# Sheet1.net
KiCad netlist of a schematic drawn in Altium Designer
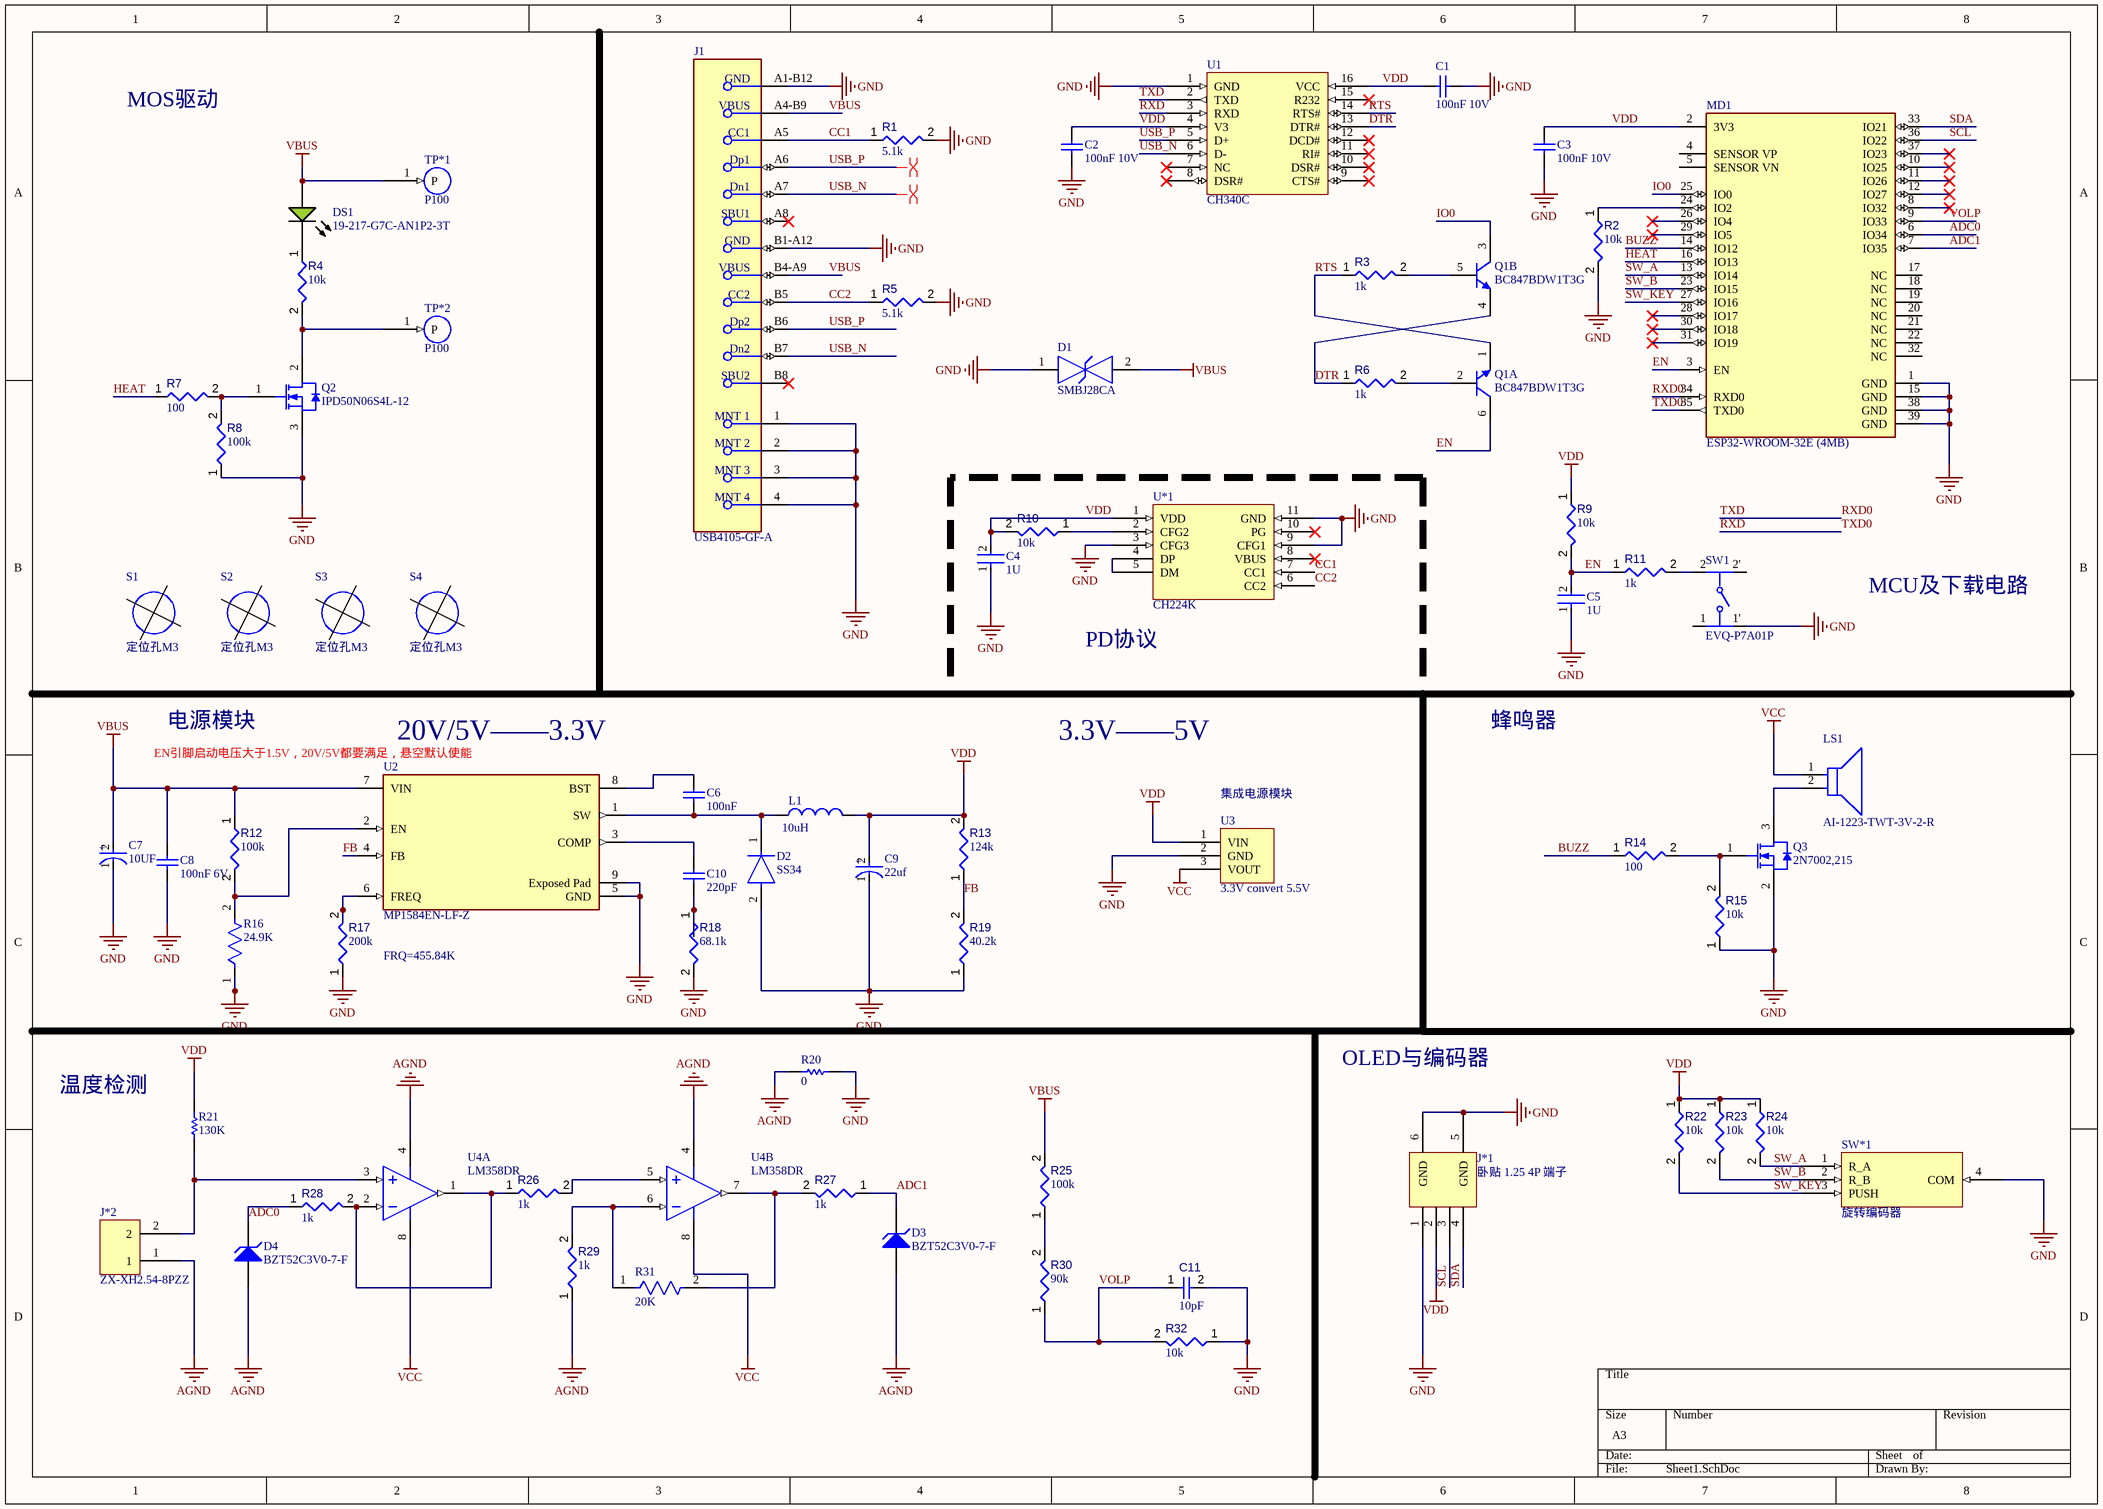
[diagram p0: Sheet1.SchDoc]

(export (version "E")
  (design (tool "Eeschema 10.0.6"))
  (components
    (comp (ref "C1")
      (value "100nF 10V")
      (footprint "CAPC0603(1608)100_M")
      (description "CAP 100nF 10V ±10% 0603 (1608 Metric) Thickness 1mm SMD")
      (fields (field (name "TOLERANCE") "Â±10%"))
      (libsource (lib "Altium Content Vault") (part "CAP"))
    )
    (comp (ref "C2")
      (value "100nF 10V")
      (footprint "CAPC0603(1608)100_M")
      (description "CAP 100nF 10V ±10% 0603 (1608 Metric) Thickness 1mm SMD")
      (fields (field (name "TOLERANCE") "Â±10%"))
      (libsource (lib "Altium Content Vault") (part "CAP"))
    )
    (comp (ref "C3")
      (value "100nF 10V")
      (footprint "CAPC0603(1608)100_M")
      (description "CAP 100nF 10V ±10% 0603 (1608 Metric) Thickness 1mm SMD")
      (fields (field (name "TOLERANCE") "Â±10%"))
      (libsource (lib "Altium Content Vault") (part "CAP"))
    )
    (comp (ref "C4")
      (value "1U")
      (footprint "FP-0603-L_1_6_0_15-W_0_81-IPC_A")
      (description "General Purpose Ceramic Capacitor, 0603, 1uF, 10%, X5R, 15%, 6.3V")
      (libsource (lib "Altium Content Vault") (part "02cd4be3c70576c341d710602a673aa"))
    )
    (comp (ref "C5")
      (value "1U")
      (footprint "FP-0603-L_1_6_0_15-W_0_81-IPC_A")
      (description "General Purpose Ceramic Capacitor, 0603, 1uF, 10%, X5R, 15%, 6.3V")
      (libsource (lib "Altium Content Vault") (part "02cd4be3c70576c341d710602a673aa"))
    )
    (comp (ref "C6")
      (value "100nF")
      (footprint "CAPC0603(1608)100_M")
      (description "CAP 100nF 10V ±10% 0603 (1608 Metric) Thickness 1mm SMD")
      (fields (field (name "TOLERANCE") "Â±10%"))
      (libsource (lib "Altium Content Vault") (part "CAP"))
    )
    (comp (ref "C7")
      (value "10UF")
      (footprint "FP-SC-MFG")
      (description "CAP ALUM 10UF 20% 35V SMD")
      (fields (field (name "TOLERANCE") "20%") (field (name "VOLTAGE") "35V"))
      (libsource (lib "Altium Content Vault") (part "203bc49f2ac43e59fd269a8c329ed05"))
    )
    (comp (ref "C8")
      (value "100nF 6V")
      (footprint "CAPC0603(1608)100_M")
      (description "CAP 100nF 10V ±10% 0603 (1608 Metric) Thickness 1mm SMD")
      (fields (field (name "TOLERANCE") "Â±10%"))
      (libsource (lib "Altium Content Vault") (part "CAP"))
    )
    (comp (ref "C9")
      (value "22uf")
      (footprint "FP-TAJC-MFG")
      (description "220uF 6.3V  ±10% 1.2Ω 2312  SMD Tantalum Capacitor")
      (fields (field (name "TOLERANCE") "10%") (field (name "VOLTAGE") "6.3V"))
      (libsource (lib "Altium Content Vault") (part "203bc49f2ac43e59fd269a8c329ed05"))
    )
    (comp (ref "C10")
      (value "220pF")
      (footprint "CAPC1608X90X35LL10T15")
      (fields (field (name "MANUFACTURER") "Murata") (field (name "PART NUMBER") "GRM1885C1H151JA01D"))
      (libsource (lib "Altium Content Vault") (part "CAP"))
    )
    (comp (ref "C11")
      (value "10pF")
      (footprint "CAPC1608X90X40ML10T20")
      (description "Chip Capacitor, 10 pF, +/- 5%, 50 V, 0603 (1608 Metric)")
      (fields (field (name "TOLERANCE") "5%") (field (name "Comment") "Capacitor 10 pF +/- 5% 50 V 0603"))
      (libsource (lib "DigiPCBA Workspace") (part "CAP-NP-2"))
    )
    (comp (ref "D1")
      (value "SMBJ28CA")
      (footprint "FP-SMBJ-CA-MFG")
      (description "TVS DIODE 28V 45.4V DO214AA")
      (fields
        (field (name "OCTOPART") "https://octopart.com/smbj28ca-littelfuse-350757")
        (field (name "MANUFACTURER") "Littelfuse Inc")
      )
      (libsource (lib "Altium Content Vault") (part "89c663e49c8877d2c9d183c2997548d"))
    )
    (comp (ref "D2")
      (value "SS34")
      (footprint "FP-95401-MFG")
      (description "DIODE GEN PURP 600V 2A DO214AA")
      (libsource (lib "Altium Content Vault") (part "d7152d700b627762746794eb795d46e"))
    )
    (comp (ref "D3")
      (value "BZT52C3V0-7-F")
      (footprint "DIOD-SOD123_V")
      (description "Surface Mount Zener Diode, 3 V, -65 to 150 degC, 2-Pin SOD123, RoHS, Tape and Reel")
      (fields (field (name "MANUFACTURER") "DiodesIncorporated"))
      (libsource (lib "Altium Content Vault") (part "DZEN-AK-2"))
    )
    (comp (ref "D4")
      (value "BZT52C3V0-7-F")
      (footprint "DIOD-SOD123_V")
      (description "Surface Mount Zener Diode, 3 V, -65 to 150 degC, 2-Pin SOD123, RoHS, Tape and Reel")
      (fields (field (name "MANUFACTURER") "DiodesIncorporated"))
      (libsource (lib "Altium Content Vault") (part "DZEN-AK-2"))
    )
    (comp (ref "DS1")
      (value "19-217-G7C-AN1P2-3T")
      (footprint "EVRL-0603-2_V")
      (description "Chip LED, Yellow-Green, 5 V, 25 mA, -40 to 85 degC, 2-Pin SMD (0603), RoHS, Tape and Reel")
      (fields (field (name "MANUFACTURER") "Everlight Electronics"))
      (libsource (lib "DigiPCBA Workspace") (part "LED-YELLOW-GREEN-AK-2"))
    )
    (comp (ref "J*1")
      (value "卧贴 1.25 4P 端子")
      (footprint "卧贴 1.25 4P 端子-Footprint-1")
      (description "ZX-MX1.25-4PJK")
      (libsource (lib "DigiPCBA Workspace") (part "卧贴 1.25 4P 端子-Symbol-1"))
    )
    (comp (ref "J*2")
      (value "ZX-XH2.54-8PZZ")
      (footprint "ZX-XH2.54-8PZZ-Footprint-1")
      (libsource (lib "DigiPCBA Workspace") (part "ZX-XH2.54-8PZZ-Symbol-1"))
    )
    (comp (ref "J1")
      (value "USB4105-GF-A")
      (footprint "FP-USB4105-GF-A-MFG")
      (description "CONN RCPT USB2.0 TYPEC 5A")
      (fields
        (field (name "MANUFACTURER") "GCT")
        (field (name "OCTOPART") "https://octopart.com/usb4105-gf-a-gct-106627878")
      )
      (libsource (lib "Altium Content Vault") (part "e7c17a616881a82b79941196b4bec10"))
    )
    (comp (ref "L1")
      (value "10uH")
      (footprint "INDM7266X28N")
      (description "SMD，7*6.6*2.8mm（0603） 合金电感，一体成型电感，大电流")
      (libsource (lib "DigiPCBA Workspace") (part "IND-2"))
    )
    (comp (ref "LS1")
      (value "AI-1223-TWT-3V-2-R")
      (footprint "FP-AI-1223-TWT-3V-2-R-MFG")
      (description "BUZZER MAGNETIC 3V 12MM TH")
      (libsource (lib "Altium Content Vault") (part "1973c4b650225fd2ddacaff6b763965"))
    )
    (comp (ref "MD1")
      (value "ESP32-WROOM-32E (4MB)")
      (footprint "FP-ESP32-WROOM-32E_4MB-MFG")
      (description "RX TXRX MOD WIFI TRACE ANT SMD")
      (libsource (lib "Altium Content Vault") (part "7f842c3463a9561e2f6f9fdcd687e0f"))
    )
    (comp (ref "Q1")
      (value "BC847BDW1T3G")
      (footprint "ONSC-SOT-363-6-419B-02_W_V")
      (description "Dual General Purpose Transistors, NPN, 6-Pin SOT-363, Pb-Free, Tape and Reel")
      (fields (field (name "MANUFACTURER") "On Semiconductor"))
      (libsource (lib "Altium Content Vault") (part "ONSC-NPN_NPN-6_F"))
    )
    (comp (ref "Q2")
      (value "IPD50N06S4L-12")
      (footprint "INF-PG-TO252-3-11_M")
      (description "OptiMOS-T2 Power-Transistor, 60 V VDS, 50 A ID, PG-TO252-3-11, Reel, Green")
      (fields (field (name "MANUFACTURER") "Infineon"))
      (libsource (lib "Altium Content Vault") (part "INF-MOSFET-N-3"))
    )
    (comp (ref "Q3")
      (value "2N7002,215")
      (footprint "NXP-SOT23-3_V")
      (fields (field (name "POWER") "830mW") (field (name "MANUFACTURER") "NXP Semiconductors"))
      (libsource (lib "DigiPCBA Workspace") (part "NEMOS-GSD-3"))
    )
    (comp (ref "R1")
      (value "5.1k")
      (footprint "RESC1608X55X25ML10T15")
      (description "Chip Resistor, 5.1 KOhm, +/- 1%, 0.1 W, -55 to 155 degC, 0603 (1608 Metric)")
      (fields (field (name "TOLERANCE") "1%") (field (name "POWER") "100mW"))
      (libsource (lib "DigiPCBA Workspace") (part "RES-2"))
    )
    (comp (ref "R2")
      (value "10k")
      (footprint "RESC1608X55X25ML10T15")
      (description "Chip Resistor, 4.7 KOhm, +/- 1%, 0.1 W, -55 to 155 degC, 0603 (1608 Metric)")
      (fields (field (name "TOLERANCE") "1%") (field (name "POWER") "100mW"))
      (libsource (lib "DigiPCBA Workspace") (part "RES-2"))
    )
    (comp (ref "R3")
      (value "1k")
      (footprint "RESC1608X55X25ML10T15")
      (description "Chip Resistor, 1 KOhm, +/-1%, 0.1 W, -55 to 155 degC, 0603 (1608 Metric)")
      (fields (field (name "POWER") "100mW") (field (name "TOLERANCE") "1%"))
      (libsource (lib "DigiPCBA Workspace") (part "RES-2"))
    )
    (comp (ref "R4")
      (value "10k")
      (footprint "RESC1608X55X25ML10T15")
      (description "Chip Resistor, 10 KOhm, +/- 1%, 01 W, -55 to 155 degC, 0603 (1608 Metric)")
      (fields (field (name "POWER") "100mW") (field (name "TOLERANCE") "1%"))
      (libsource (lib "DigiPCBA Workspace") (part "RES-2"))
    )
    (comp (ref "R5")
      (value "5.1k")
      (footprint "RESC1608X55X25ML10T15")
      (description "Chip Resistor, 4.7 KOhm, +/- 1%, 0.1 W, -55 to 155 degC, 0603 (1608 Metric)")
      (fields (field (name "TOLERANCE") "1%") (field (name "POWER") "100mW"))
      (libsource (lib "DigiPCBA Workspace") (part "RES-2"))
    )
    (comp (ref "R6")
      (value "1k")
      (footprint "RESC1608X55X25ML10T15")
      (description "Chip Resistor, 1 KOhm, +/-1%, 0.1 W, -55 to 155 degC, 0603 (1608 Metric)")
      (fields (field (name "POWER") "100mW") (field (name "TOLERANCE") "1%"))
      (libsource (lib "DigiPCBA Workspace") (part "RES-2"))
    )
    (comp (ref "R7")
      (value "100")
      (footprint "RESC0603(1608)_L")
      (description "120R 0.1W 5% 0603 (1608 Metric)  SMD")
      (fields (field (name "POWER") "100mW") (field (name "TOLERANCE") "5%"))
      (libsource (lib "DigiPCBA Workspace") (part "120R3J"))
    )
    (comp (ref "R8")
      (value "100k")
      (footprint "RESC1608X55X25ML10T15")
      (description "Chip Resistor, 100 KOhm, +/- 1%, 0.1 W, -55 to 155 degC, 0603 (1608 Metric)")
      (fields (field (name "TOLERANCE") "1%") (field (name "POWER") "100mW"))
      (libsource (lib "DigiPCBA Workspace") (part "RES-2"))
    )
    (comp (ref "R9")
      (value "10k")
      (footprint "RESC1608X55X25ML10T15")
      (description "Chip Resistor, 4.7 KOhm, +/- 1%, 0.1 W, -55 to 155 degC, 0603 (1608 Metric)")
      (fields (field (name "TOLERANCE") "1%") (field (name "POWER") "100mW"))
      (libsource (lib "DigiPCBA Workspace") (part "RES-2"))
    )
    (comp (ref "R10")
      (value "10k")
      (footprint "RESC1608X55X25ML10T15")
      (description "Chip Resistor, 4.7 KOhm, +/- 1%, 0.1 W, -55 to 155 degC, 0603 (1608 Metric)")
      (fields (field (name "TOLERANCE") "1%") (field (name "POWER") "100mW"))
      (libsource (lib "DigiPCBA Workspace") (part "RES-2"))
    )
    (comp (ref "R11")
      (value "1k")
      (footprint "RESC1608X55X25ML10T15")
      (description "Chip Resistor, 4.7 KOhm, +/- 1%, 0.1 W, -55 to 155 degC, 0603 (1608 Metric)")
      (fields (field (name "TOLERANCE") "1%") (field (name "POWER") "100mW"))
      (libsource (lib "DigiPCBA Workspace") (part "RES-2"))
    )
    (comp (ref "R12")
      (value "100k")
      (footprint "RESC1608X55X25ML10T15")
      (description "Chip Resistor, 100 KOhm, +/- 1%, 0.1 W, -55 to 155 degC, 0603 (1608 Metric)")
      (fields (field (name "TOLERANCE") "1%") (field (name "POWER") "100mW"))
      (libsource (lib "DigiPCBA Workspace") (part "RES-2"))
    )
    (comp (ref "R13")
      (value "124k")
      (footprint "RESC1608X55X25ML10T15")
      (description "Chip Resistor, 100 KOhm, +/- 1%, 0.1 W, -55 to 155 degC, 0603 (1608 Metric)")
      (fields (field (name "TOLERANCE") "1%") (field (name "POWER") "100mW"))
      (libsource (lib "DigiPCBA Workspace") (part "RES-2"))
    )
    (comp (ref "R14")
      (value "100")
      (footprint "RESC0603(1608)_L")
      (description "120R 0.1W 5% 0603 (1608 Metric)  SMD")
      (fields (field (name "POWER") "100mW") (field (name "TOLERANCE") "5%"))
      (libsource (lib "DigiPCBA Workspace") (part "120R3J"))
    )
    (comp (ref "R15")
      (value "10k")
      (footprint "RESC1608X55X25ML10T15")
      (description "Chip Resistor, 10 KOhm, +/- 1%, 01 W, -55 to 155 degC, 0603 (1608 Metric)")
      (fields (field (name "POWER") "100mW") (field (name "TOLERANCE") "1%"))
      (libsource (lib "DigiPCBA Workspace") (part "RES-2"))
    )
    (comp (ref "R16")
      (value "24.9K")
      (footprint "FP-RC_L0603-MFG")
      (description "RES SMD 24.9K OHM 1% 1/10W 0603")
      (fields (field (name "MANUFACTURER PART NUMBER") "RC0603FR-0724K9L") (field (name "VOLTAGE") "75V"))
      (libsource (lib "Altium Content Vault") (part "1029c3af85768c4190bb7ad29bc67b5"))
    )
    (comp (ref "R17")
      (value "200k")
      (footprint "RESC1608X55X25ML10T15")
      (description "Chip Resistor, 100 KOhm, +/- 1%, 0.1 W, -55 to 155 degC, 0603 (1608 Metric)")
      (fields (field (name "TOLERANCE") "1%") (field (name "POWER") "100mW"))
      (libsource (lib "DigiPCBA Workspace") (part "RES-2"))
    )
    (comp (ref "R18")
      (value "68.1k")
      (footprint "RESC1608X55X25ML10T15")
      (description "Chip Resistor, 100 KOhm, +/- 1%, 0.1 W, -55 to 155 degC, 0603 (1608 Metric)")
      (fields (field (name "TOLERANCE") "1%") (field (name "POWER") "100mW"))
      (libsource (lib "DigiPCBA Workspace") (part "RES-2"))
    )
    (comp (ref "R19")
      (value "40.2k")
      (footprint "RESC1608X55X25ML10T15")
      (description "Chip Resistor, 100 KOhm, +/- 1%, 0.1 W, -55 to 155 degC, 0603 (1608 Metric)")
      (fields (field (name "TOLERANCE") "1%") (field (name "POWER") "100mW"))
      (libsource (lib "DigiPCBA Workspace") (part "RES-2"))
    )
    (comp (ref "R20")
      (value "0")
      (footprint "RESC1608X55X25ML10T15")
      (description "Chip Resistor, 0 Ohm, 0.1 W, -55 to 155 degC, 0603 (1608 Metric)")
      (fields (field (name "POWER") "100mW") (field (name "TOLERANCE") "5%"))
      (libsource (lib "") (part "RES-2_1"))
    )
    (comp (ref "R21")
      (value "130K")
      (footprint "RESC1609X50X30NL10T20")
      (fields (field (name "MANUFACTURER") "Vishay Dale") (field (name "PART NUMBER") "CRCW0603130KFKEA"))
      (libsource (lib "Altium Content Vault") (part "RES"))
    )
    (comp (ref "R22")
      (value "10k")
      (footprint "RESC1608X55X25ML10T15")
      (description "Chip Resistor, 10 KOhm, +/- 1%, 01 W, -55 to 155 degC, 0603 (1608 Metric)")
      (fields (field (name "POWER") "100mW") (field (name "TOLERANCE") "1%"))
      (libsource (lib "DigiPCBA Workspace") (part "RES-2"))
    )
    (comp (ref "R23")
      (value "10k")
      (footprint "RESC1608X55X25ML10T15")
      (description "Chip Resistor, 10 KOhm, +/- 1%, 01 W, -55 to 155 degC, 0603 (1608 Metric)")
      (fields (field (name "POWER") "100mW") (field (name "TOLERANCE") "1%"))
      (libsource (lib "DigiPCBA Workspace") (part "RES-2"))
    )
    (comp (ref "R24")
      (value "10k")
      (footprint "RESC1608X55X25ML10T15")
      (description "Chip Resistor, 10 KOhm, +/- 1%, 01 W, -55 to 155 degC, 0603 (1608 Metric)")
      (fields (field (name "POWER") "100mW") (field (name "TOLERANCE") "1%"))
      (libsource (lib "DigiPCBA Workspace") (part "RES-2"))
    )
    (comp (ref "R25")
      (value "100k")
      (footprint "RESC1608X55X25ML10T15")
      (description "Chip Resistor, 100 KOhm, +/- 1%, 0.1 W, -55 to 155 degC, 0603 (1608 Metric)")
      (fields (field (name "TOLERANCE") "1%") (field (name "POWER") "100mW"))
      (libsource (lib "DigiPCBA Workspace") (part "RES-2"))
    )
    (comp (ref "R26")
      (value "1k")
      (footprint "RESC1608X55X25ML10T15")
      (description "Chip Resistor, 4.7 KOhm, +/- 1%, 0.1 W, -55 to 155 degC, 0603 (1608 Metric)")
      (fields (field (name "TOLERANCE") "1%") (field (name "POWER") "100mW"))
      (libsource (lib "DigiPCBA Workspace") (part "RES-2"))
    )
    (comp (ref "R27")
      (value "1k")
      (footprint "RESC1608X55X25ML10T15")
      (description "Chip Resistor, 4.7 KOhm, +/- 1%, 0.1 W, -55 to 155 degC, 0603 (1608 Metric)")
      (fields (field (name "TOLERANCE") "1%") (field (name "POWER") "100mW"))
      (libsource (lib "DigiPCBA Workspace") (part "RES-2"))
    )
    (comp (ref "R28")
      (value "1k")
      (footprint "RESC1608X55X25ML10T15")
      (description "Chip Resistor, 1 KOhm, +/-1%, 0.1 W, -55 to 155 degC, 0603 (1608 Metric)")
      (fields (field (name "POWER") "100mW") (field (name "TOLERANCE") "1%"))
      (libsource (lib "DigiPCBA Workspace") (part "RES-2"))
    )
    (comp (ref "R29")
      (value "1k")
      (footprint "RESC1608X55X25ML10T15")
      (description "Chip Resistor, 4.7 KOhm, +/- 1%, 0.1 W, -55 to 155 degC, 0603 (1608 Metric)")
      (fields (field (name "TOLERANCE") "1%") (field (name "POWER") "100mW"))
      (libsource (lib "DigiPCBA Workspace") (part "RES-2"))
    )
    (comp (ref "R30")
      (value "90k")
      (footprint "RESC1608X55X25ML10T15")
      (description "Chip Resistor, 100 KOhm, +/- 1%, 0.1 W, -55 to 155 degC, 0603 (1608 Metric)")
      (fields (field (name "TOLERANCE") "1%") (field (name "POWER") "100mW"))
      (libsource (lib "DigiPCBA Workspace") (part "RES-2"))
    )
    (comp (ref "R31")
      (value "20K")
      (footprint "FP-RC0603-0_55-IPC_C")
      (description "RES 20K OHM 1% 1/10W 0603")
      (libsource (lib "Altium Content Vault") (part "1029c3af85768c4190bb7ad29bc67b5"))
    )
    (comp (ref "R32")
      (value "10k")
      (footprint "RESC1608X55X25ML10T15")
      (description "Chip Resistor, 10 KOhm, +/- 1%, 01 W, -55 to 155 degC, 0603 (1608 Metric)")
      (fields (field (name "POWER") "100mW") (field (name "TOLERANCE") "1%"))
      (libsource (lib "DigiPCBA Workspace") (part "RES-2"))
    )
    (comp (ref "S1")
      (value "定位孔M3")
      (footprint "定位孔M3-Footprint-1")
      (description "M3定位孔")
      (libsource (lib "DigiPCBA Workspace") (part "定位孔M3-Symbol-1"))
    )
    (comp (ref "S2")
      (value "定位孔M3")
      (footprint "定位孔M3-Footprint-1")
      (description "M3定位孔")
      (libsource (lib "DigiPCBA Workspace") (part "定位孔M3-Symbol-1"))
    )
    (comp (ref "S3")
      (value "定位孔M3")
      (footprint "定位孔M3-Footprint-1")
      (description "M3定位孔")
      (libsource (lib "DigiPCBA Workspace") (part "定位孔M3-Symbol-1"))
    )
    (comp (ref "S4")
      (value "定位孔M3")
      (footprint "定位孔M3-Footprint-1")
      (description "M3定位孔")
      (libsource (lib "DigiPCBA Workspace") (part "定位孔M3-Symbol-1"))
    )
    (comp (ref "SW*1")
      (value "旋转编码器")
      (footprint "旋转编码器-Footprint-1")
      (description "MITSUMI  SIQ-02FVS3")
      (libsource (lib "DigiPCBA Workspace") (part "旋转编码器-Symbol-1"))
    )
    (comp (ref "SW1")
      (value "EVQ-P7A01P")
      (footprint "FP-EVQ-P7A01P-MFG")
      (description "Switch Tactile N.O. SPST Rectangular Button Gull Wing 0.05A 12VDC 2.2N SMD Embossed T/R")
      (libsource (lib "DigiPCBA Workspace") (part "c93661f14280f1e5a1fd29b4a471f7d"))
    )
    (comp (ref "TP*1")
      (value "P100")
      (footprint "P100-Footprint-1")
      (description "测试探针 3A")
      (libsource (lib "DigiPCBA Workspace") (part "P100-Symbol-1"))
    )
    (comp (ref "TP*2")
      (value "P100")
      (footprint "P100-Footprint-1")
      (description "测试探针 3A")
      (libsource (lib "DigiPCBA Workspace") (part "P100-Symbol-1"))
    )
    (comp (ref "U*1")
      (value "CH224K")
      (footprint "SOP100P610X180_HS-12N")
      (description "USB PD等多快充协议受电芯片CH224")
      (libsource (lib "DigiPCBA Workspace") (part "CH224K-Symbol-1"))
    )
    (comp (ref "U1")
      (value "CH340C")
      (footprint "SOP127P610X180-16N")
      (description "USB转串")
      (libsource (lib "DigiPCBA Workspace") (part "CH340C"))
    )
    (comp (ref "U2")
      (value "MP1584EN-LF-Z")
      (footprint "FP-MP1584EN-LF-Z-MFG")
      (description "IC REG BUCK ADJ 3A")
      (fields
        (field (name "OCTOPART") "https://octopart.com/mp1584en-lf-z-monolithic+power+systems-18629680")
        (field (name "MANUFACTURER") "Monolithic Power Systems")
      )
      (libsource (lib "Altium Content Vault") (part "4a11bbc70e04dd5d8e18f8ee926335f"))
    )
    (comp (ref "U3")
      (value "3.3V convert 5.5V")
      (footprint "3.3V convert 5.5V-Footprint-1")
      (description "迷你升压模块")
      (libsource (lib "DigiPCBA Workspace") (part "3.3V convert 5.5V-Symbol-1"))
    )
    (comp (ref "U4")
      (value "LM358DR")
      (footprint "D0008A_L")
      (fields (field (name "MANUFACTURER") "Texas Instruments (TI)"))
      (libsource (lib "DigiPCBA Workspace") (part "TI-LM358-8"))
    )
  )
  (nets
    (net (code "1") (name "/ADC0") (class "Default")
      (node (ref "D4") (pin "2") (pinfunction "K_2") (pintype "passive"))
      (node (ref "MD1") (pin "6") (pinfunction "IO34_6") (pintype "bidirectional"))
      (node (ref "R28") (pin "1") (pinfunction "1_1") (pintype "passive"))
    )
    (net (code "2") (name "/ADC1") (class "Default")
      (node (ref "D3") (pin "2") (pinfunction "K_2") (pintype "passive"))
      (node (ref "MD1") (pin "7") (pinfunction "IO35_7") (pintype "bidirectional"))
      (node (ref "R27") (pin "1") (pinfunction "1_1") (pintype "passive"))
    )
    (net (code "3") (name "/BUZZ") (class "Default")
      (node (ref "MD1") (pin "14") (pinfunction "IO12_14") (pintype "bidirectional"))
      (node (ref "R14") (pin "1") (pinfunction "1_1") (pintype "passive"))
    )
    (net (code "4") (name "/CC1") (class "Default")
      (node (ref "J1") (pin "A5") (pinfunction "CC1_A5") (pintype "power_in"))
      (node (ref "R1") (pin "1") (pinfunction "1_1") (pintype "passive"))
      (node (ref "U*1") (pin "7") (pinfunction "CC1_7") (pintype "input"))
    )
    (net (code "5") (name "/CC2") (class "Default")
      (node (ref "J1") (pin "B5") (pinfunction "CC2_B5") (pintype "bidirectional"))
      (node (ref "R5") (pin "1") (pinfunction "1_1") (pintype "passive"))
      (node (ref "U*1") (pin "6") (pinfunction "CC2_6") (pintype "input"))
    )
    (net (code "6") (name "/DTR") (class "Default")
      (node (ref "Q1") (pin "4") (pinfunction "E_4") (pintype "passive"))
      (node (ref "R6") (pin "1") (pinfunction "1_1") (pintype "passive"))
      (node (ref "U1") (pin "13") (pinfunction "DTR#_13") (pintype "bidirectional"))
    )
    (net (code "7") (name "/EN") (class "Default")
      (node (ref "C5") (pin "2") (pinfunction "2_2") (pintype "passive"))
      (node (ref "MD1") (pin "3") (pinfunction "EN_3") (pintype "input"))
      (node (ref "Q1") (pin "6") (pinfunction "C_6") (pintype "passive"))
      (node (ref "R11") (pin "1") (pinfunction "1_1") (pintype "passive"))
      (node (ref "R9") (pin "2") (pinfunction "2_2") (pintype "passive"))
    )
    (net (code "8") (name "/FB") (class "Default")
      (node (ref "R13") (pin "1") (pinfunction "1_1") (pintype "passive"))
      (node (ref "R19") (pin "2") (pinfunction "2_2") (pintype "passive"))
      (node (ref "U2") (pin "4") (pinfunction "FB_4") (pintype "input"))
    )
    (net (code "9") (name "/HEAT") (class "Default")
      (node (ref "MD1") (pin "16") (pinfunction "IO13_16") (pintype "bidirectional"))
      (node (ref "R7") (pin "1") (pinfunction "1_1") (pintype "passive"))
    )
    (net (code "10") (name "/IO0") (class "Default")
      (node (ref "MD1") (pin "25") (pinfunction "IO0_25") (pintype "bidirectional"))
      (node (ref "Q1") (pin "3") (pinfunction "C_3") (pintype "passive"))
    )
    (net (code "11") (name "/RTS") (class "Default")
      (node (ref "Q1") (pin "1") (pinfunction "E_1") (pintype "passive"))
      (node (ref "R3") (pin "1") (pinfunction "1_1") (pintype "passive"))
      (node (ref "U1") (pin "14") (pinfunction "RTS#_14") (pintype "bidirectional"))
    )
    (net (code "12") (name "/RXD") (class "Default")
      (node (ref "MD1") (pin "35") (pinfunction "TXD0_35") (pintype "output"))
      (node (ref "U1") (pin "3") (pinfunction "RXD_3") (pintype "input"))
    )
    (net (code "13") (name "/RXD0") (class "Default")
      (node (ref "MD1") (pin "34") (pinfunction "RXD0_34") (pintype "input"))
      (node (ref "U1") (pin "2") (pinfunction "TXD_2") (pintype "output"))
    )
    (net (code "14") (name "/SCL") (class "Default")
      (node (ref "J*1") (pin "3") (pinfunction "3_3") (pintype "passive"))
      (node (ref "MD1") (pin "36") (pinfunction "IO22_36") (pintype "bidirectional"))
    )
    (net (code "15") (name "/SDA") (class "Default")
      (node (ref "J*1") (pin "4") (pinfunction "4_4") (pintype "passive"))
      (node (ref "MD1") (pin "33") (pinfunction "IO21_33") (pintype "bidirectional"))
    )
    (net (code "16") (name "/SW_A") (class "Default")
      (node (ref "MD1") (pin "13") (pinfunction "IO14_13") (pintype "bidirectional"))
      (node (ref "R24") (pin "2") (pinfunction "2_2") (pintype "passive"))
      (node (ref "SW*1") (pin "1") (pinfunction "R_A_1") (pintype "input"))
    )
    (net (code "17") (name "/SW_B") (class "Default")
      (node (ref "MD1") (pin "23") (pinfunction "IO15_23") (pintype "bidirectional"))
      (node (ref "R23") (pin "2") (pinfunction "2_2") (pintype "passive"))
      (node (ref "SW*1") (pin "2") (pinfunction "R_B_2") (pintype "input"))
    )
    (net (code "18") (name "/SW_KEY") (class "Default")
      (node (ref "MD1") (pin "27") (pinfunction "IO16_27") (pintype "bidirectional"))
      (node (ref "R22") (pin "2") (pinfunction "2_2") (pintype "passive"))
      (node (ref "SW*1") (pin "3") (pinfunction "PUSH_3") (pintype "input"))
    )
    (net (code "19") (name "/USB_N") (class "Default")
      (node (ref "J1") (pin "A7") (pinfunction "Dn1_A7") (pintype "bidirectional"))
      (node (ref "J1") (pin "B7") (pinfunction "Dn2_B7") (pintype "bidirectional"))
      (node (ref "U1") (pin "6") (pinfunction "D-_6") (pintype "input"))
    )
    (net (code "20") (name "/USB_P") (class "Default")
      (node (ref "J1") (pin "A6") (pinfunction "Dp1_A6") (pintype "bidirectional"))
      (node (ref "J1") (pin "B6") (pinfunction "Dp2_B6") (pintype "bidirectional"))
      (node (ref "U1") (pin "5") (pinfunction "D+_5") (pintype "input"))
    )
    (net (code "21") (name "/VOLP") (class "Default")
      (node (ref "C11") (pin "1") (pinfunction "1_1") (pintype "passive"))
      (node (ref "MD1") (pin "9") (pinfunction "IO33_9") (pintype "bidirectional"))
      (node (ref "R30") (pin "1") (pinfunction "1_1") (pintype "passive"))
      (node (ref "R32") (pin "2") (pinfunction "2_2") (pintype "passive"))
    )
    (net (code "22") (name "AGND") (class "Default")
      (node (ref "D3") (pin "1") (pinfunction "A_1") (pintype "passive"))
      (node (ref "D4") (pin "1") (pinfunction "A_1") (pintype "passive"))
      (node (ref "J*2") (pin "1") (pinfunction "1_1") (pintype "passive"))
      (node (ref "R20") (pin "1") (pinfunction "1_1") (pintype "passive"))
      (node (ref "R29") (pin "1") (pinfunction "1_1") (pintype "passive"))
      (node (ref "U4") (pin "4") (pinfunction "GND_4") (pintype "power_in"))
    )
    (net (code "23") (name "GND") (class "Default")
      (node (ref "C1") (pin "2") (pinfunction "2_2") (pintype "passive"))
      (node (ref "C11") (pin "2") (pinfunction "2_2") (pintype "passive"))
      (node (ref "C2") (pin "1") (pinfunction "1_1") (pintype "passive"))
      (node (ref "C3") (pin "2") (pinfunction "2_2") (pintype "passive"))
      (node (ref "C4") (pin "1") (pinfunction "1_1") (pintype "passive"))
      (node (ref "C5") (pin "1") (pinfunction "1_1") (pintype "passive"))
      (node (ref "C7") (pin "1") (pinfunction "C_1") (pintype "passive"))
      (node (ref "C8") (pin "1") (pinfunction "1_1") (pintype "passive"))
      (node (ref "C9") (pin "1") (pinfunction "C_1") (pintype "passive"))
      (node (ref "D1") (pin "1") (pinfunction "1_1") (pintype "passive"))
      (node (ref "D2") (pin "2") (pinfunction "A_2") (pintype "passive"))
      (node (ref "J*1") (pin "1") (pinfunction "1_1") (pintype "passive"))
      (node (ref "J*1") (pin "5") (pinfunction "GND_5") (pintype "passive"))
      (node (ref "J*1") (pin "6") (pinfunction "GND_6") (pintype "passive"))
      (node (ref "J1") (pin "1") (pinfunction "MNT_1_1") (pintype "power_in"))
      (node (ref "J1") (pin "2") (pinfunction "MNT_2_2") (pintype "power_in"))
      (node (ref "J1") (pin "3") (pinfunction "MNT_3_3") (pintype "power_in"))
      (node (ref "J1") (pin "4") (pinfunction "MNT_4_4") (pintype "power_in"))
      (node (ref "J1") (pin "A1-B12") (pinfunction "GND_A1-B12") (pintype "power_in"))
      (node (ref "J1") (pin "B1-A12") (pinfunction "GND_B1-A12") (pintype "bidirectional"))
      (node (ref "MD1") (pin "1") (pinfunction "GND_1") (pintype "power_in"))
      (node (ref "MD1") (pin "15") (pinfunction "GND_15") (pintype "power_in"))
      (node (ref "MD1") (pin "38") (pinfunction "GND_38") (pintype "power_in"))
      (node (ref "MD1") (pin "39") (pinfunction "GND_39") (pintype "power_in"))
      (node (ref "Q2") (pin "3") (pinfunction "SOURCE_3") (pintype "passive"))
      (node (ref "Q3") (pin "2") (pinfunction "S_2") (pintype "passive"))
      (node (ref "R1") (pin "2") (pinfunction "2_2") (pintype "passive"))
      (node (ref "R15") (pin "1") (pinfunction "1_1") (pintype "passive"))
      (node (ref "R16") (pin "1") (pinfunction "1_1") (pintype "passive"))
      (node (ref "R17") (pin "1") (pinfunction "1_1") (pintype "passive"))
      (node (ref "R18") (pin "2") (pinfunction "2_2") (pintype "passive"))
      (node (ref "R19") (pin "1") (pinfunction "1_1") (pintype "passive"))
      (node (ref "R2") (pin "2") (pinfunction "2_2") (pintype "passive"))
      (node (ref "R20") (pin "2") (pinfunction "2_2") (pintype "passive"))
      (node (ref "R32") (pin "1") (pinfunction "1_1") (pintype "passive"))
      (node (ref "R5") (pin "2") (pinfunction "2_2") (pintype "passive"))
      (node (ref "R8") (pin "1") (pinfunction "1_1") (pintype "passive"))
      (node (ref "SW*1") (pin "4") (pinfunction "COM_4") (pintype "input"))
      (node (ref "SW1") (pin "1'") (pinfunction "1'_1'") (pintype "passive"))
      (node (ref "U*1") (pin "11") (pinfunction "GND_11") (pintype "input"))
      (node (ref "U*1") (pin "3") (pinfunction "CFG3_3") (pintype "input"))
      (node (ref "U*1") (pin "9") (pinfunction "CFG1_9") (pintype "input"))
      (node (ref "U1") (pin "1") (pinfunction "GND_1") (pintype "input"))
      (node (ref "U2") (pin "5") (pinfunction "GND_5") (pintype "power_in"))
      (node (ref "U2") (pin "9") (pinfunction "Exposed_Pad_9") (pintype "power_in"))
      (node (ref "U3") (pin "2") (pinfunction "GND_2") (pintype "passive"))
    )
    (net (code "24") (name "Net-(C10-Pad2)") (class "Default")
      (node (ref "C10") (pin "2") (pinfunction "2_2") (pintype "passive"))
      (node (ref "R18") (pin "1") (pinfunction "1_1") (pintype "passive"))
    )
    (net (code "25") (name "Net-(D2-C)") (class "Default")
      (node (ref "C6") (pin "1") (pinfunction "1_1") (pintype "passive"))
      (node (ref "D2") (pin "1") (pinfunction "C_1") (pintype "passive"))
      (node (ref "L1") (pin "1") (pinfunction "1_1") (pintype "passive"))
      (node (ref "U2") (pin "1") (pinfunction "SW_1") (pintype "output"))
    )
    (net (code "26") (name "Net-(DS1-K)") (class "Default")
      (node (ref "DS1") (pin "2") (pinfunction "K_2") (pintype "passive"))
      (node (ref "R4") (pin "1") (pinfunction "1_1") (pintype "passive"))
    )
    (net (code "27") (name "Net-(LS1-A)") (class "Default")
      (node (ref "LS1") (pin "2") (pinfunction "A_2") (pintype "passive"))
      (node (ref "Q3") (pin "3") (pinfunction "D_3") (pintype "passive"))
    )
    (net (code "28") (name "Net-(MD1-IO2)") (class "Default")
      (node (ref "MD1") (pin "24") (pinfunction "IO2_24") (pintype "bidirectional"))
      (node (ref "R2") (pin "1") (pinfunction "1_1") (pintype "passive"))
    )
    (net (code "29") (name "Net-(Q1A-B)") (class "Default")
      (node (ref "Q1") (pin "2") (pinfunction "B_2") (pintype "passive"))
      (node (ref "R6") (pin "2") (pinfunction "2_2") (pintype "passive"))
    )
    (net (code "30") (name "Net-(Q1B-B)") (class "Default")
      (node (ref "Q1") (pin "5") (pinfunction "B_5") (pintype "passive"))
      (node (ref "R3") (pin "2") (pinfunction "2_2") (pintype "passive"))
    )
    (net (code "31") (name "Net-(Q2-DRAIN)") (class "Default")
      (node (ref "Q2") (pin "2") (pinfunction "DRAIN_2") (pintype "passive"))
      (node (ref "R4") (pin "2") (pinfunction "2_2") (pintype "passive"))
      (node (ref "TP*2") (pin "1") (pinfunction "P_1") (pintype "input"))
    )
    (net (code "32") (name "Net-(Q2-GATE)") (class "Default")
      (node (ref "Q2") (pin "1") (pinfunction "GATE_1") (pintype "passive"))
      (node (ref "R7") (pin "2") (pinfunction "2_2") (pintype "passive"))
      (node (ref "R8") (pin "2") (pinfunction "2_2") (pintype "passive"))
    )
    (net (code "33") (name "Net-(Q3-G)") (class "Default")
      (node (ref "Q3") (pin "1") (pinfunction "G_1") (pintype "passive"))
      (node (ref "R14") (pin "2") (pinfunction "2_2") (pintype "passive"))
      (node (ref "R15") (pin "2") (pinfunction "2_2") (pintype "passive"))
    )
    (net (code "34") (name "Net-(R11-Pad2)") (class "Default")
      (node (ref "R11") (pin "2") (pinfunction "2_2") (pintype "passive"))
      (node (ref "SW1") (pin "2") (pinfunction "2_2") (pintype "passive"))
    )
    (net (code "35") (name "Net-(R25-Pad1)") (class "Default")
      (node (ref "R25") (pin "1") (pinfunction "1_1") (pintype "passive"))
      (node (ref "R30") (pin "2") (pinfunction "2_2") (pintype "passive"))
    )
    (net (code "36") (name "Net-(U*1-CFG2)") (class "Default")
      (node (ref "R10") (pin "1") (pinfunction "1_1") (pintype "passive"))
      (node (ref "U*1") (pin "2") (pinfunction "CFG2_2") (pintype "input"))
    )
    (net (code "37") (name "Net-(U*1-DM)") (class "Default")
      (node (ref "U*1") (pin "4") (pinfunction "DP_4") (pintype "passive"))
      (node (ref "U*1") (pin "5") (pinfunction "DM_5") (pintype "passive"))
    )
    (net (code "38") (name "Net-(U2-BST)") (class "Default")
      (node (ref "C6") (pin "2") (pinfunction "2_2") (pintype "passive"))
      (node (ref "U2") (pin "8") (pinfunction "BST_8") (pintype "power_in"))
    )
    (net (code "39") (name "Net-(U2-COMP)") (class "Default")
      (node (ref "C10") (pin "1") (pinfunction "1_1") (pintype "passive"))
      (node (ref "U2") (pin "3") (pinfunction "COMP_3") (pintype "output"))
    )
    (net (code "40") (name "Net-(U2-EN)") (class "Default")
      (node (ref "R12") (pin "2") (pinfunction "2_2") (pintype "passive"))
      (node (ref "R16") (pin "2") (pinfunction "2_2") (pintype "passive"))
      (node (ref "U2") (pin "2") (pinfunction "EN_2") (pintype "input"))
    )
    (net (code "41") (name "Net-(U2-FREQ)") (class "Default")
      (node (ref "R17") (pin "2") (pinfunction "2_2") (pintype "passive"))
      (node (ref "U2") (pin "6") (pinfunction "FREQ_6") (pintype "input"))
    )
    (net (code "42") (name "Net-(U4A-1IN+)") (class "Default")
      (node (ref "J*2") (pin "2") (pinfunction "2_2") (pintype "passive"))
      (node (ref "R21") (pin "1") (pinfunction "1_1") (pintype "passive"))
      (node (ref "U4") (pin "3") (pinfunction "1IN+_3") (pintype "input"))
    )
    (net (code "43") (name "Net-(U4A-1IN-)") (class "Default")
      (node (ref "R26") (pin "1") (pinfunction "1_1") (pintype "passive"))
      (node (ref "R28") (pin "2") (pinfunction "2_2") (pintype "passive"))
      (node (ref "U4") (pin "1") (pinfunction "1OUT_1") (pintype "output"))
      (node (ref "U4") (pin "2") (pinfunction "1IN-_2") (pintype "input"))
    )
    (net (code "44") (name "Net-(U4B-2IN+)") (class "Default")
      (node (ref "R26") (pin "2") (pinfunction "2_2") (pintype "passive"))
      (node (ref "U4") (pin "5") (pinfunction "2IN+_5") (pintype "input"))
    )
    (net (code "45") (name "Net-(U4B-2IN-)") (class "Default")
      (node (ref "R29") (pin "2") (pinfunction "2_2") (pintype "passive"))
      (node (ref "R31") (pin "1") (pinfunction "1_1") (pintype "passive"))
      (node (ref "U4") (pin "6") (pinfunction "2IN-_6") (pintype "input"))
    )
    (net (code "46") (name "Net-(U4B-2OUT)") (class "Default")
      (node (ref "R27") (pin "2") (pinfunction "2_2") (pintype "passive"))
      (node (ref "R31") (pin "2") (pinfunction "2_2") (pintype "passive"))
      (node (ref "U4") (pin "7") (pinfunction "2OUT_7") (pintype "output"))
    )
    (net (code "47") (name "VBUS") (class "Default")
      (node (ref "C7") (pin "2") (pinfunction "A_2") (pintype "passive"))
      (node (ref "C8") (pin "2") (pinfunction "2_2") (pintype "passive"))
      (node (ref "D1") (pin "2") (pinfunction "2_2") (pintype "passive"))
      (node (ref "DS1") (pin "1") (pinfunction "A_1") (pintype "passive"))
      (node (ref "J1") (pin "A4-B9") (pinfunction "VBUS_A4-B9") (pintype "power_in"))
      (node (ref "J1") (pin "B4-A9") (pinfunction "VBUS_B4-A9") (pintype "bidirectional"))
      (node (ref "R12") (pin "1") (pinfunction "1_1") (pintype "passive"))
      (node (ref "R25") (pin "2") (pinfunction "2_2") (pintype "passive"))
      (node (ref "TP*1") (pin "1") (pinfunction "P_1") (pintype "input"))
      (node (ref "U2") (pin "7") (pinfunction "VIN_7") (pintype "power_in"))
    )
    (net (code "48") (name "VCC") (class "Default")
      (node (ref "LS1") (pin "1") (pinfunction "C_1") (pintype "passive"))
      (node (ref "U3") (pin "3") (pinfunction "VOUT_3") (pintype "power_in"))
      (node (ref "U4") (pin "8") (pinfunction "VCC_8") (pintype "power_in"))
    )
    (net (code "49") (name "VDD") (class "Default")
      (node (ref "C1") (pin "1") (pinfunction "1_1") (pintype "passive"))
      (node (ref "C2") (pin "2") (pinfunction "2_2") (pintype "passive"))
      (node (ref "C3") (pin "1") (pinfunction "1_1") (pintype "passive"))
      (node (ref "C4") (pin "2") (pinfunction "2_2") (pintype "passive"))
      (node (ref "C9") (pin "2") (pinfunction "A_2") (pintype "passive"))
      (node (ref "J*1") (pin "2") (pinfunction "2_2") (pintype "passive"))
      (node (ref "L1") (pin "2") (pinfunction "2_2") (pintype "passive"))
      (node (ref "MD1") (pin "2") (pinfunction "3V3_2") (pintype "power_in"))
      (node (ref "R10") (pin "2") (pinfunction "2_2") (pintype "passive"))
      (node (ref "R13") (pin "2") (pinfunction "2_2") (pintype "passive"))
      (node (ref "R21") (pin "2") (pinfunction "2_2") (pintype "passive"))
      (node (ref "R22") (pin "1") (pinfunction "1_1") (pintype "passive"))
      (node (ref "R23") (pin "1") (pinfunction "1_1") (pintype "passive"))
      (node (ref "R24") (pin "1") (pinfunction "1_1") (pintype "passive"))
      (node (ref "R9") (pin "1") (pinfunction "1_1") (pintype "passive"))
      (node (ref "U*1") (pin "1") (pinfunction "VDD_1") (pintype "input"))
      (node (ref "U1") (pin "16") (pinfunction "VCC_16") (pintype "input"))
      (node (ref "U1") (pin "4") (pinfunction "V3_4") (pintype "input"))
      (node (ref "U3") (pin "1") (pinfunction "VIN_1") (pintype "power_in"))
    )
    (net (code "50") (name "unconnected-(J1-SBU1-PadA8)") (class "Default")
      (node (ref "J1") (pin "A8") (pinfunction "SBU1_A8") (pintype "bidirectional+no_connect"))
    )
    (net (code "51") (name "unconnected-(J1-SBU2-PadB8)") (class "Default")
      (node (ref "J1") (pin "B8") (pinfunction "SBU2_B8") (pintype "power_in+no_connect"))
    )
    (net (code "52") (name "unconnected-(MD1-IO4-Pad26)") (class "Default")
      (node (ref "MD1") (pin "26") (pinfunction "IO4_26") (pintype "bidirectional+no_connect"))
    )
    (net (code "53") (name "unconnected-(MD1-IO5-Pad29)") (class "Default")
      (node (ref "MD1") (pin "29") (pinfunction "IO5_29") (pintype "bidirectional+no_connect"))
    )
    (net (code "54") (name "unconnected-(MD1-IO17-Pad28)") (class "Default")
      (node (ref "MD1") (pin "28") (pinfunction "IO17_28") (pintype "bidirectional+no_connect"))
    )
    (net (code "55") (name "unconnected-(MD1-IO18-Pad30)") (class "Default")
      (node (ref "MD1") (pin "30") (pinfunction "IO18_30") (pintype "bidirectional+no_connect"))
    )
    (net (code "56") (name "unconnected-(MD1-IO19-Pad31)") (class "Default")
      (node (ref "MD1") (pin "31") (pinfunction "IO19_31") (pintype "bidirectional+no_connect"))
    )
    (net (code "57") (name "unconnected-(MD1-IO23-Pad37)") (class "Default")
      (node (ref "MD1") (pin "37") (pinfunction "IO23_37") (pintype "bidirectional+no_connect"))
    )
    (net (code "58") (name "unconnected-(MD1-IO25-Pad10)") (class "Default")
      (node (ref "MD1") (pin "10") (pinfunction "IO25_10") (pintype "bidirectional+no_connect"))
    )
    (net (code "59") (name "unconnected-(MD1-IO26-Pad11)") (class "Default")
      (node (ref "MD1") (pin "11") (pinfunction "IO26_11") (pintype "bidirectional+no_connect"))
    )
    (net (code "60") (name "unconnected-(MD1-IO27-Pad12)") (class "Default")
      (node (ref "MD1") (pin "12") (pinfunction "IO27_12") (pintype "bidirectional+no_connect"))
    )
    (net (code "61") (name "unconnected-(MD1-IO32-Pad8)") (class "Default")
      (node (ref "MD1") (pin "8") (pinfunction "IO32_8") (pintype "bidirectional+no_connect"))
    )
    (net (code "62") (name "unconnected-(MD1-NC-Pad17)") (class "Default")
      (node (ref "MD1") (pin "17") (pinfunction "NC_17") (pintype "passive"))
    )
    (net (code "63") (name "unconnected-(MD1-NC-Pad18)") (class "Default")
      (node (ref "MD1") (pin "18") (pinfunction "NC_18") (pintype "passive"))
    )
    (net (code "64") (name "unconnected-(MD1-NC-Pad19)") (class "Default")
      (node (ref "MD1") (pin "19") (pinfunction "NC_19") (pintype "passive"))
    )
    (net (code "65") (name "unconnected-(MD1-NC-Pad20)") (class "Default")
      (node (ref "MD1") (pin "20") (pinfunction "NC_20") (pintype "passive"))
    )
    (net (code "66") (name "unconnected-(MD1-NC-Pad21)") (class "Default")
      (node (ref "MD1") (pin "21") (pinfunction "NC_21") (pintype "passive"))
    )
    (net (code "67") (name "unconnected-(MD1-NC-Pad22)") (class "Default")
      (node (ref "MD1") (pin "22") (pinfunction "NC_22") (pintype "passive"))
    )
    (net (code "68") (name "unconnected-(MD1-NC-Pad32)") (class "Default")
      (node (ref "MD1") (pin "32") (pinfunction "NC_32") (pintype "passive"))
    )
    (net (code "69") (name "unconnected-(MD1-SENSOR_VN-Pad5)") (class "Default")
      (node (ref "MD1") (pin "5") (pinfunction "SENSOR_VN_5") (pintype "passive"))
    )
    (net (code "70") (name "unconnected-(MD1-SENSOR_VP-Pad4)") (class "Default")
      (node (ref "MD1") (pin "4") (pinfunction "SENSOR_VP_4") (pintype "passive"))
    )
    (net (code "71") (name "unconnected-(SW1-Pad1)") (class "Default")
      (node (ref "SW1") (pin "1") (pinfunction "1_1") (pintype "passive"))
    )
    (net (code "72") (name "unconnected-(SW1-Pad2')") (class "Default")
      (node (ref "SW1") (pin "2'") (pinfunction "2'_2'") (pintype "passive"))
    )
    (net (code "73") (name "unconnected-(U*1-PG-Pad10)") (class "Default")
      (node (ref "U*1") (pin "10") (pinfunction "PG_10") (pintype "input+no_connect"))
    )
    (net (code "74") (name "unconnected-(U*1-VBUS-Pad8)") (class "Default")
      (node (ref "U*1") (pin "8") (pinfunction "VBUS_8") (pintype "input+no_connect"))
    )
    (net (code "75") (name "unconnected-(U1-CTS#-Pad9)") (class "Default")
      (node (ref "U1") (pin "9") (pinfunction "CTS#_9") (pintype "bidirectional+no_connect"))
    )
    (net (code "76") (name "unconnected-(U1-DCD#-Pad12)") (class "Default")
      (node (ref "U1") (pin "12") (pinfunction "DCD#_12") (pintype "bidirectional+no_connect"))
    )
    (net (code "77") (name "unconnected-(U1-DSR#-Pad8)") (class "Default")
      (node (ref "U1") (pin "8") (pinfunction "DSR#_8") (pintype "bidirectional+no_connect"))
    )
    (net (code "78") (name "unconnected-(U1-DSR#-Pad10)") (class "Default")
      (node (ref "U1") (pin "10") (pinfunction "DSR#_10") (pintype "bidirectional+no_connect"))
    )
    (net (code "79") (name "unconnected-(U1-NC-Pad7)") (class "Default")
      (node (ref "U1") (pin "7") (pinfunction "NC_7") (pintype "input+no_connect"))
    )
    (net (code "80") (name "unconnected-(U1-R232-Pad15)") (class "Default")
      (node (ref "U1") (pin "15") (pinfunction "R232_15") (pintype "input+no_connect"))
    )
    (net (code "81") (name "unconnected-(U1-RI#-Pad11)") (class "Default")
      (node (ref "U1") (pin "11") (pinfunction "RI#_11") (pintype "bidirectional+no_connect"))
    )
  )
)
